# DIY_037.net
KiCad netlist of a schematic drawn in EAGLE
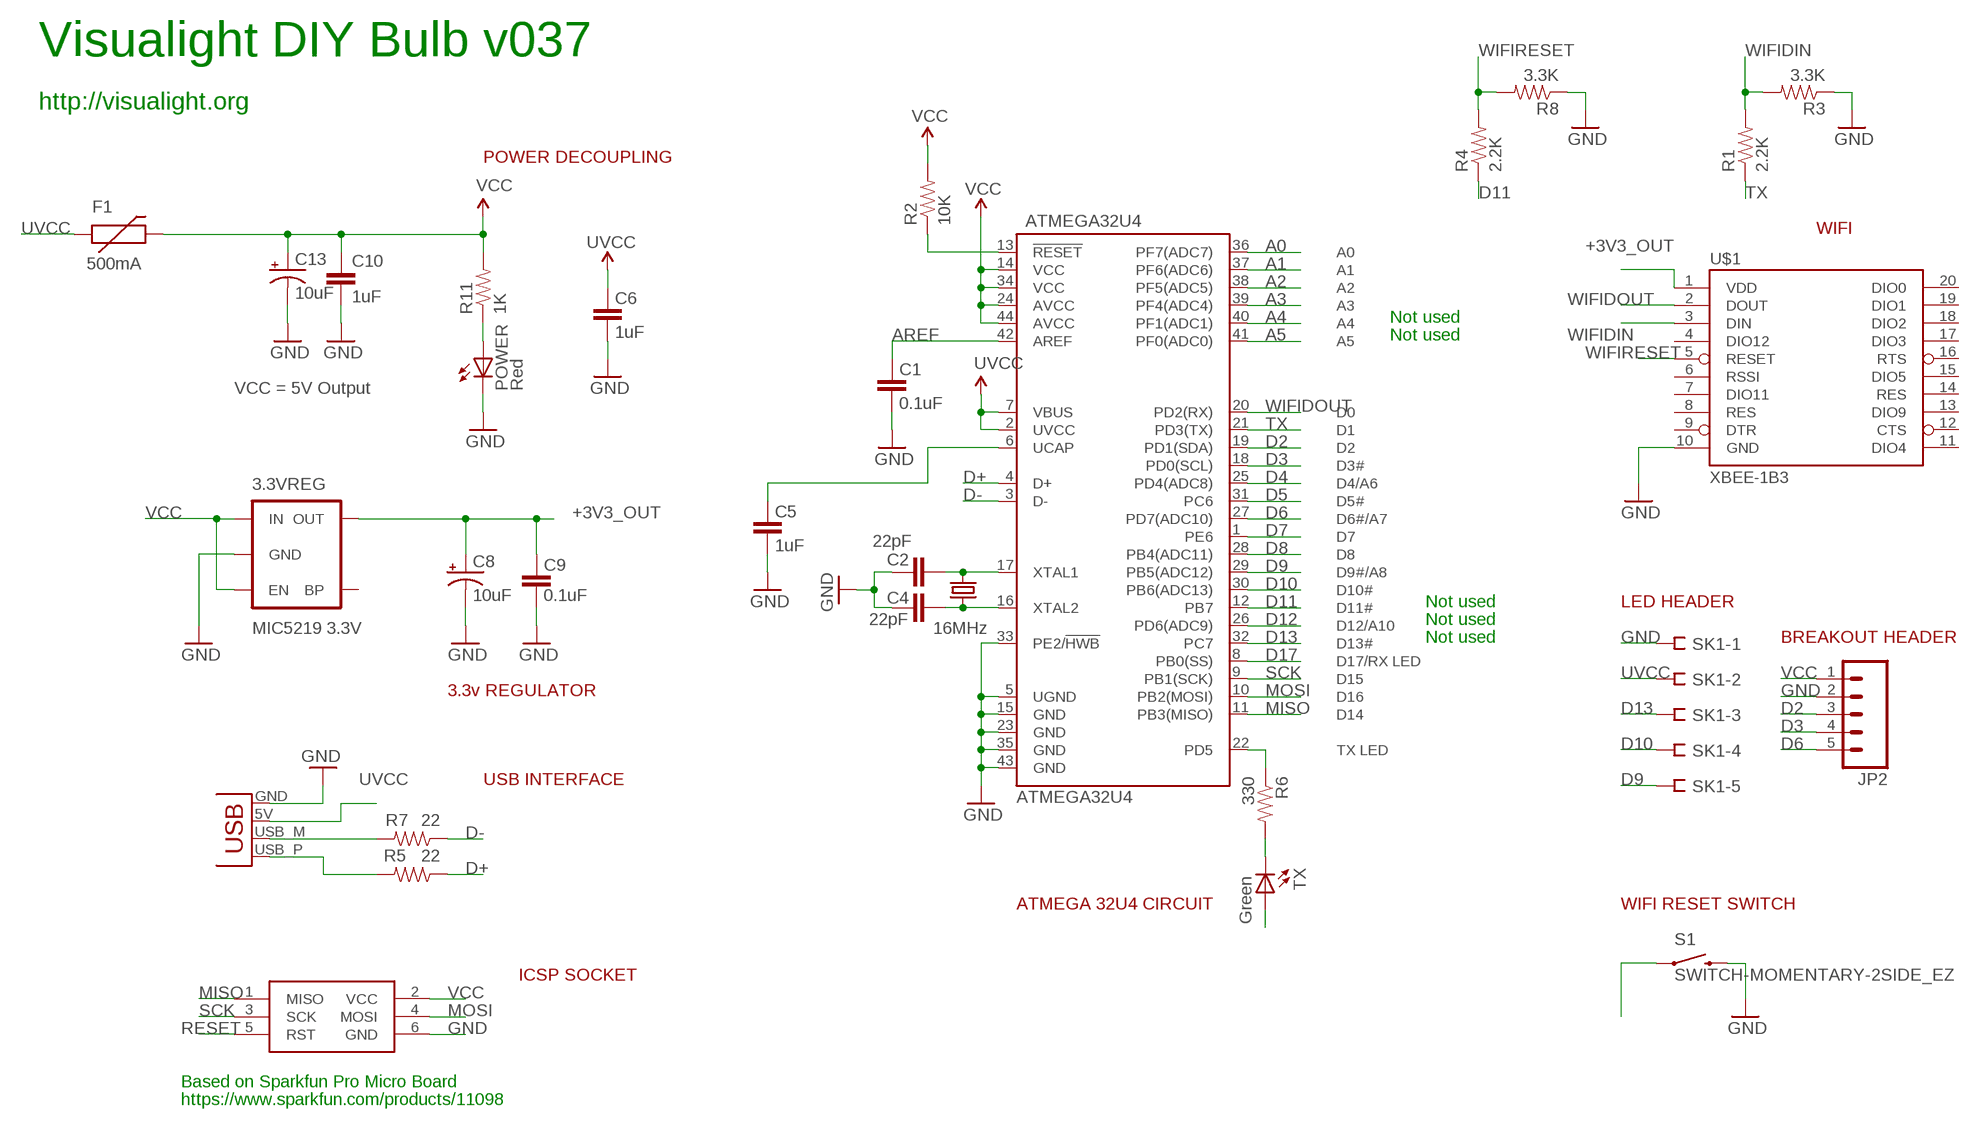
[diagram p0: schematic, sheet 1]

(export (version "E")
  (design (tool "Eeschema 10.0.6"))
  (components
    (comp (ref "3.3VREG")
      (value "MIC5219 3.3V")
      (footprint "eagle-import:SOT23-5")
      (libsource (lib "eagle-import") (part "V_REG_MIC52193.3V"))
    )
    (comp (ref "ATMEGA32U4")
      (value "ATMEGA32U4")
      (footprint "eagle-import:SPARKFUN-DIGITALIC_TQFP44")
      (libsource (lib "eagle-import") (part "ATMEGA32U4TQFP"))
    )
    (comp (ref "C1")
      (value "0.1uF")
      (footprint "eagle-import:0402-CAP")
      (libsource (lib "eagle-import") (part "CAP0402-CAP"))
    )
    (comp (ref "C2")
      (value "22pF")
      (footprint "eagle-import:0402-CAP")
      (libsource (lib "eagle-import") (part "CAP0402-CAP"))
    )
    (comp (ref "C4")
      (value "22pF")
      (footprint "eagle-import:0402-CAP")
      (libsource (lib "eagle-import") (part "CAP0402-CAP"))
    )
    (comp (ref "C5")
      (value "1uF")
      (footprint "eagle-import:0402-CAP")
      (libsource (lib "eagle-import") (part "CAP0402-CAP"))
    )
    (comp (ref "C6")
      (value "1uF")
      (footprint "eagle-import:0402-CAP")
      (libsource (lib "eagle-import") (part "CAP0402-CAP"))
    )
    (comp (ref "C8")
      (value "10uF")
      (footprint "eagle-import:EIA3216")
      (libsource (lib "eagle-import") (part "CAP_POL1206"))
    )
    (comp (ref "C9")
      (value "0.1uF")
      (footprint "eagle-import:0402-CAP")
      (libsource (lib "eagle-import") (part "CAP0402-CAP"))
    )
    (comp (ref "C10")
      (value "1uF")
      (footprint "eagle-import:0402-CAP")
      (libsource (lib "eagle-import") (part "CAP0402-CAP"))
    )
    (comp (ref "C13")
      (value "10uF")
      (footprint "eagle-import:EIA3216")
      (libsource (lib "eagle-import") (part "CAP_POL1206"))
    )
    (comp (ref "F1")
      (value "500mA")
      (footprint "eagle-import:PTC-1206")
      (libsource (lib "eagle-import") (part "PTCSMD"))
    )
    (comp (ref "ISP1")
      (value "AVRISP-6")
      (footprint "eagle-import:AVRISP")
      (libsource (lib "eagle-import") (part "AVRISP-6"))
    )
    (comp (ref "JP2")
      (value "M05PTH")
      (footprint "eagle-import:1X05")
      (libsource (lib "eagle-import") (part "M05PTH"))
    )
    (comp (ref "POWER")
      (value "Red")
      (footprint "eagle-import:LED-0603")
      (libsource (lib "eagle-import") (part "LED0603"))
    )
    (comp (ref "R1")
      (value "2.2K")
      (footprint "eagle-import:0402-RES")
      (libsource (lib "eagle-import") (part "RESISTOR0402-RES"))
    )
    (comp (ref "R2")
      (value "10K")
      (footprint "eagle-import:0402-RES")
      (libsource (lib "eagle-import") (part "RESISTOR0402-RES"))
    )
    (comp (ref "R3")
      (value "3.3K")
      (footprint "eagle-import:0402-RES")
      (libsource (lib "eagle-import") (part "RESISTOR0402-RES"))
    )
    (comp (ref "R4")
      (value "2.2K")
      (footprint "eagle-import:0402-RES")
      (libsource (lib "eagle-import") (part "RESISTOR0402-RES"))
    )
    (comp (ref "R5")
      (value "22")
      (footprint "eagle-import:0402-RES")
      (libsource (lib "eagle-import") (part "RESISTOR0402-RES"))
    )
    (comp (ref "R6")
      (value "330")
      (footprint "eagle-import:0402-RES")
      (libsource (lib "eagle-import") (part "RESISTOR0402-RES"))
    )
    (comp (ref "R7")
      (value "22")
      (footprint "eagle-import:0402-RES")
      (libsource (lib "eagle-import") (part "RESISTOR0402-RES"))
    )
    (comp (ref "R8")
      (value "3.3K")
      (footprint "eagle-import:0402-RES")
      (libsource (lib "eagle-import") (part "RESISTOR0402-RES"))
    )
    (comp (ref "R11")
      (value "1K")
      (footprint "eagle-import:0402-RES")
      (libsource (lib "eagle-import") (part "RESISTOR0402-RES"))
    )
    (comp (ref "S1")
      (value "SWITCH-MOMENTARY-2SIDE_EZ")
      (footprint "eagle-import:TACTILE-PTH-SIDEEZ")
      (libsource (lib "eagle-import") (part "SWITCH-MOMENTARY-2SIDE_EZ"))
    )
    (comp (ref "SK1")
      (value "DF3-05S")
      (footprint "eagle-import:DF3S-05")
      (libsource (lib "eagle-import") (part "DF3-05S"))
    )
    (comp (ref "TX")
      (value "Green")
      (footprint "eagle-import:LED-0603")
      (libsource (lib "eagle-import") (part "LED0603"))
    )
    (comp (ref "U$1")
      (value "XBEE-1B3")
      (footprint "eagle-import:XBEE-SMD")
      (libsource (lib "eagle-import") (part "XBEE-1B3"))
    )
    (comp (ref "X2")
      (value "USBPCB")
      (footprint "eagle-import:USB-A-PCB")
      (libsource (lib "eagle-import") (part "USBPCB"))
    )
    (comp (ref "Y1")
      (value "16MHz")
      (footprint "eagle-import:CRYSTAL-SMD-5X3")
      (libsource (lib "eagle-import") (part "CRYSTAL5X3"))
    )
  )
  (nets
    (net (code "1") (name "/+3V3_OUT") (class "Default")
      (node (ref "3.3VREG") (pin "5") (pinfunction "OUT_5") (pintype "passive"))
      (node (ref "C8") (pin "A") (pinfunction "+_A") (pintype "passive"))
      (node (ref "C9") (pin "2") (pinfunction "2_2") (pintype "passive"))
      (node (ref "U$1") (pin "1") (pinfunction "VDD_1") (pintype "power_in"))
    )
    (net (code "2") (name "/A0") (class "Default")
      (node (ref "ATMEGA32U4") (pin "36") (pinfunction "PF7(ADC7)_36") (pintype "bidirectional"))
    )
    (net (code "3") (name "/A1") (class "Default")
      (node (ref "ATMEGA32U4") (pin "37") (pinfunction "PF6(ADC6)_37") (pintype "bidirectional"))
    )
    (net (code "4") (name "/A2") (class "Default")
      (node (ref "ATMEGA32U4") (pin "38") (pinfunction "PF5(ADC5)_38") (pintype "bidirectional"))
    )
    (net (code "5") (name "/A3") (class "Default")
      (node (ref "ATMEGA32U4") (pin "39") (pinfunction "PF4(ADC4)_39") (pintype "bidirectional"))
    )
    (net (code "6") (name "/A4") (class "Default")
      (node (ref "ATMEGA32U4") (pin "40") (pinfunction "PF1(ADC1)_40") (pintype "bidirectional"))
    )
    (net (code "7") (name "/A5") (class "Default")
      (node (ref "ATMEGA32U4") (pin "41") (pinfunction "PF0(ADC0)_41") (pintype "bidirectional"))
    )
    (net (code "8") (name "/AREF") (class "Default")
      (node (ref "ATMEGA32U4") (pin "42") (pinfunction "AREF_42") (pintype "bidirectional"))
      (node (ref "C1") (pin "2") (pinfunction "2_2") (pintype "passive"))
    )
    (net (code "9") (name "/D+") (class "Default")
      (node (ref "ATMEGA32U4") (pin "4") (pinfunction "D+_4") (pintype "bidirectional"))
      (node (ref "R5") (pin "1") (pinfunction "1_1") (pintype "passive"))
    )
    (net (code "10") (name "/D-") (class "Default")
      (node (ref "ATMEGA32U4") (pin "3") (pinfunction "D-_3") (pintype "bidirectional"))
      (node (ref "R7") (pin "1") (pinfunction "1_1") (pintype "passive"))
    )
    (net (code "11") (name "/D2") (class "Default")
      (node (ref "ATMEGA32U4") (pin "19") (pinfunction "PD1(SDA)_19") (pintype "bidirectional"))
      (node (ref "JP2") (pin "3") (pinfunction "3_3") (pintype "passive"))
    )
    (net (code "12") (name "/D3") (class "Default")
      (node (ref "ATMEGA32U4") (pin "18") (pinfunction "PD0(SCL)_18") (pintype "bidirectional"))
      (node (ref "JP2") (pin "4") (pinfunction "4_4") (pintype "passive"))
    )
    (net (code "13") (name "/D4") (class "Default")
      (node (ref "ATMEGA32U4") (pin "25") (pinfunction "PD4(ADC8)_25") (pintype "bidirectional"))
    )
    (net (code "14") (name "/D5") (class "Default")
      (node (ref "ATMEGA32U4") (pin "31") (pinfunction "PC6_31") (pintype "bidirectional"))
    )
    (net (code "15") (name "/D6") (class "Default")
      (node (ref "ATMEGA32U4") (pin "27") (pinfunction "PD7(ADC10)_27") (pintype "bidirectional"))
      (node (ref "JP2") (pin "5") (pinfunction "5_5") (pintype "passive"))
    )
    (net (code "16") (name "/D7") (class "Default")
      (node (ref "ATMEGA32U4") (pin "1") (pinfunction "PE6_1") (pintype "bidirectional"))
      (node (ref "S1") (pin "1") (pinfunction "1_1") (pintype "passive"))
    )
    (net (code "17") (name "/D8") (class "Default")
      (node (ref "ATMEGA32U4") (pin "28") (pinfunction "PB4(ADC11)_28") (pintype "bidirectional"))
    )
    (net (code "18") (name "/D9") (class "Default")
      (node (ref "ATMEGA32U4") (pin "29") (pinfunction "PB5(ADC12)_29") (pintype "bidirectional"))
      (node (ref "SK1") (pin "5") (pinfunction "S_5") (pintype "passive"))
    )
    (net (code "19") (name "/D10") (class "Default")
      (node (ref "ATMEGA32U4") (pin "30") (pinfunction "PB6(ADC13)_30") (pintype "bidirectional"))
      (node (ref "SK1") (pin "4") (pinfunction "S_4") (pintype "passive"))
    )
    (net (code "20") (name "/D11") (class "Default")
      (node (ref "ATMEGA32U4") (pin "12") (pinfunction "PB7_12") (pintype "bidirectional"))
      (node (ref "R4") (pin "1") (pinfunction "1_1") (pintype "passive"))
    )
    (net (code "21") (name "/D12") (class "Default")
      (node (ref "ATMEGA32U4") (pin "26") (pinfunction "PD6(ADC9)_26") (pintype "bidirectional"))
    )
    (net (code "22") (name "/D13") (class "Default")
      (node (ref "ATMEGA32U4") (pin "32") (pinfunction "PC7_32") (pintype "bidirectional"))
      (node (ref "SK1") (pin "3") (pinfunction "S_3") (pintype "passive"))
    )
    (net (code "23") (name "/D17") (class "Default")
      (node (ref "ATMEGA32U4") (pin "8") (pinfunction "PB0(SS)_8") (pintype "bidirectional"))
    )
    (net (code "24") (name "/MISO") (class "Default")
      (node (ref "ATMEGA32U4") (pin "11") (pinfunction "PB3(MISO)_11") (pintype "bidirectional"))
      (node (ref "ISP1") (pin "1") (pinfunction "MISO_1") (pintype "input"))
    )
    (net (code "25") (name "/MOSI") (class "Default")
      (node (ref "ATMEGA32U4") (pin "10") (pinfunction "PB2(MOSI)_10") (pintype "bidirectional"))
      (node (ref "ISP1") (pin "4") (pinfunction "MOSI_4") (pintype "output"))
    )
    (net (code "26") (name "/RESET") (class "Default")
      (node (ref "ATMEGA32U4") (pin "13") (pinfunction "~{RESET}_13") (pintype "bidirectional"))
      (node (ref "ISP1") (pin "5") (pinfunction "RST_5") (pintype "output"))
      (node (ref "R2") (pin "1") (pinfunction "1_1") (pintype "passive"))
    )
    (net (code "27") (name "/SCK") (class "Default")
      (node (ref "ATMEGA32U4") (pin "9") (pinfunction "PB1(SCK)_9") (pintype "bidirectional"))
      (node (ref "ISP1") (pin "3") (pinfunction "SCK_3") (pintype "output"))
    )
    (net (code "28") (name "/TX") (class "Default")
      (node (ref "ATMEGA32U4") (pin "21") (pinfunction "PD3(TX)_21") (pintype "bidirectional"))
      (node (ref "R1") (pin "1") (pinfunction "1_1") (pintype "passive"))
    )
    (net (code "29") (name "/WIFIDIN") (class "Default")
      (node (ref "R1") (pin "2") (pinfunction "2_2") (pintype "passive"))
      (node (ref "R3") (pin "2") (pinfunction "2_2") (pintype "passive"))
      (node (ref "U$1") (pin "3") (pinfunction "DIN_3") (pintype "input"))
    )
    (net (code "30") (name "/WIFIDOUT") (class "Default")
      (node (ref "ATMEGA32U4") (pin "20") (pinfunction "PD2(RX)_20") (pintype "bidirectional"))
      (node (ref "U$1") (pin "2") (pinfunction "DOUT_2") (pintype "output"))
    )
    (net (code "31") (name "/WIFIRESET") (class "Default")
      (node (ref "R4") (pin "2") (pinfunction "2_2") (pintype "passive"))
      (node (ref "R8") (pin "2") (pinfunction "2_2") (pintype "passive"))
      (node (ref "U$1") (pin "5") (pinfunction "RESET_5") (pintype "input"))
    )
    (net (code "32") (name "GND") (class "Default")
      (node (ref "3.3VREG") (pin "2") (pinfunction "GND_2") (pintype "input"))
      (node (ref "ATMEGA32U4") (pin "15") (pinfunction "GND_15") (pintype "bidirectional"))
      (node (ref "ATMEGA32U4") (pin "23") (pinfunction "GND_23") (pintype "bidirectional"))
      (node (ref "ATMEGA32U4") (pin "33") (pinfunction "PE2/~{HWB}_33") (pintype "bidirectional"))
      (node (ref "ATMEGA32U4") (pin "35") (pinfunction "GND_35") (pintype "bidirectional"))
      (node (ref "ATMEGA32U4") (pin "43") (pinfunction "GND_43") (pintype "bidirectional"))
      (node (ref "ATMEGA32U4") (pin "5") (pinfunction "UGND_5") (pintype "bidirectional"))
      (node (ref "C1") (pin "1") (pinfunction "1_1") (pintype "passive"))
      (node (ref "C10") (pin "2") (pinfunction "2_2") (pintype "passive"))
      (node (ref "C13") (pin "C") (pinfunction "-_C") (pintype "passive"))
      (node (ref "C2") (pin "2") (pinfunction "2_2") (pintype "passive"))
      (node (ref "C4") (pin "2") (pinfunction "2_2") (pintype "passive"))
      (node (ref "C5") (pin "1") (pinfunction "1_1") (pintype "passive"))
      (node (ref "C6") (pin "1") (pinfunction "1_1") (pintype "passive"))
      (node (ref "C8") (pin "C") (pinfunction "-_C") (pintype "passive"))
      (node (ref "C9") (pin "1") (pinfunction "1_1") (pintype "passive"))
      (node (ref "ISP1") (pin "6") (pinfunction "GND_6") (pintype "power_in"))
      (node (ref "JP2") (pin "2") (pinfunction "2_2") (pintype "passive"))
      (node (ref "POWER") (pin "C") (pinfunction "C_C") (pintype "passive"))
      (node (ref "R3") (pin "1") (pinfunction "1_1") (pintype "passive"))
      (node (ref "R8") (pin "1") (pinfunction "1_1") (pintype "passive"))
      (node (ref "S1") (pin "2") (pinfunction "2_2") (pintype "passive"))
      (node (ref "SK1") (pin "1") (pinfunction "S_1") (pintype "passive"))
      (node (ref "U$1") (pin "10") (pinfunction "GND_10") (pintype "power_in"))
      (node (ref "X2") (pin "GND") (pinfunction "GND_GND") (pintype "bidirectional"))
    )
    (net (code "33") (name "Net-(ATMEGA32U4-PD5)") (class "Default")
      (node (ref "ATMEGA32U4") (pin "22") (pinfunction "PD5_22") (pintype "bidirectional"))
      (node (ref "R6") (pin "1") (pinfunction "1_1") (pintype "passive"))
    )
    (net (code "34") (name "Net-(ATMEGA32U4-UCAP)") (class "Default")
      (node (ref "ATMEGA32U4") (pin "6") (pinfunction "UCAP_6") (pintype "bidirectional"))
      (node (ref "C5") (pin "2") (pinfunction "2_2") (pintype "passive"))
    )
    (net (code "35") (name "Net-(ATMEGA32U4-XTAL1)") (class "Default")
      (node (ref "ATMEGA32U4") (pin "17") (pinfunction "XTAL1_17") (pintype "bidirectional"))
      (node (ref "C2") (pin "1") (pinfunction "1_1") (pintype "passive"))
      (node (ref "Y1") (pin "3") (pinfunction "2_3") (pintype "passive"))
    )
    (net (code "36") (name "Net-(ATMEGA32U4-XTAL2)") (class "Default")
      (node (ref "ATMEGA32U4") (pin "16") (pinfunction "XTAL2_16") (pintype "bidirectional"))
      (node (ref "C4") (pin "1") (pinfunction "1_1") (pintype "passive"))
      (node (ref "Y1") (pin "1") (pinfunction "1_1") (pintype "passive"))
    )
    (net (code "37") (name "Net-(POWER-PadA)") (class "Default")
      (node (ref "POWER") (pin "A") (pinfunction "A_A") (pintype "passive"))
      (node (ref "R11") (pin "1") (pinfunction "1_1") (pintype "passive"))
    )
    (net (code "38") (name "Net-(R6-Pad2)") (class "Default")
      (node (ref "R6") (pin "2") (pinfunction "2_2") (pintype "passive"))
      (node (ref "TX") (pin "C") (pinfunction "C_C") (pintype "passive"))
    )
    (net (code "39") (name "Net-(X2-D+)") (class "Default")
      (node (ref "R5") (pin "2") (pinfunction "2_2") (pintype "passive"))
      (node (ref "X2") (pin "USB_P") (pinfunction "D+_USB_P") (pintype "bidirectional"))
    )
    (net (code "40") (name "Net-(X2-D-)") (class "Default")
      (node (ref "R7") (pin "2") (pinfunction "2_2") (pintype "passive"))
      (node (ref "X2") (pin "USB_M") (pinfunction "D-_USB_M") (pintype "bidirectional"))
    )
    (net (code "41") (name "UVCC") (class "Default")
      (node (ref "ATMEGA32U4") (pin "2") (pinfunction "UVCC_2") (pintype "bidirectional"))
      (node (ref "ATMEGA32U4") (pin "7") (pinfunction "VBUS_7") (pintype "bidirectional"))
      (node (ref "C6") (pin "2") (pinfunction "2_2") (pintype "passive"))
      (node (ref "F1") (pin "1") (pinfunction "1_1") (pintype "bidirectional"))
      (node (ref "SK1") (pin "2") (pinfunction "S_2") (pintype "passive"))
      (node (ref "X2") (pin "5V") (pinfunction "VBUS_5V") (pintype "bidirectional"))
    )
    (net (code "42") (name "VCC") (class "Default")
      (node (ref "3.3VREG") (pin "1") (pinfunction "IN_1") (pintype "input"))
      (node (ref "3.3VREG") (pin "3") (pinfunction "EN_3") (pintype "input"))
      (node (ref "ATMEGA32U4") (pin "14") (pinfunction "VCC_14") (pintype "bidirectional"))
      (node (ref "ATMEGA32U4") (pin "24") (pinfunction "AVCC_24") (pintype "bidirectional"))
      (node (ref "ATMEGA32U4") (pin "34") (pinfunction "VCC_34") (pintype "bidirectional"))
      (node (ref "ATMEGA32U4") (pin "44") (pinfunction "AVCC_44") (pintype "bidirectional"))
      (node (ref "C10") (pin "1") (pinfunction "1_1") (pintype "passive"))
      (node (ref "C13") (pin "A") (pinfunction "+_A") (pintype "passive"))
      (node (ref "F1") (pin "2") (pinfunction "2_2") (pintype "bidirectional"))
      (node (ref "ISP1") (pin "2") (pinfunction "VCC_2") (pintype "power_in"))
      (node (ref "JP2") (pin "1") (pinfunction "1_1") (pintype "passive"))
      (node (ref "R11") (pin "2") (pinfunction "2_2") (pintype "passive"))
      (node (ref "R2") (pin "2") (pinfunction "2_2") (pintype "passive"))
      (node (ref "TX") (pin "A") (pinfunction "A_A") (pintype "passive"))
    )
    (net (code "43") (name "unconnected-(3.3VREG-BP-Pad4)") (class "Default")
      (node (ref "3.3VREG") (pin "4") (pinfunction "BP_4") (pintype "input"))
    )
    (net (code "44") (name "unconnected-(U$1-CTS-Pad12)") (class "Default")
      (node (ref "U$1") (pin "12") (pinfunction "CTS_12") (pintype "output"))
    )
    (net (code "45") (name "unconnected-(U$1-DIO0-Pad20)") (class "Default")
      (node (ref "U$1") (pin "20") (pinfunction "DIO0_20") (pintype "bidirectional"))
    )
    (net (code "46") (name "unconnected-(U$1-DIO1-Pad19)") (class "Default")
      (node (ref "U$1") (pin "19") (pinfunction "DIO1_19") (pintype "bidirectional"))
    )
    (net (code "47") (name "unconnected-(U$1-DIO2-Pad18)") (class "Default")
      (node (ref "U$1") (pin "18") (pinfunction "DIO2_18") (pintype "bidirectional"))
    )
    (net (code "48") (name "unconnected-(U$1-DIO3-Pad17)") (class "Default")
      (node (ref "U$1") (pin "17") (pinfunction "DIO3_17") (pintype "bidirectional"))
    )
    (net (code "49") (name "unconnected-(U$1-DIO4-Pad11)") (class "Default")
      (node (ref "U$1") (pin "11") (pinfunction "DIO4_11") (pintype "bidirectional"))
    )
    (net (code "50") (name "unconnected-(U$1-DIO5-Pad15)") (class "Default")
      (node (ref "U$1") (pin "15") (pinfunction "DIO5_15") (pintype "bidirectional"))
    )
    (net (code "51") (name "unconnected-(U$1-DIO9-Pad13)") (class "Default")
      (node (ref "U$1") (pin "13") (pinfunction "DIO9_13") (pintype "bidirectional"))
    )
    (net (code "52") (name "unconnected-(U$1-DIO11-Pad7)") (class "Default")
      (node (ref "U$1") (pin "7") (pinfunction "DIO11_7") (pintype "bidirectional"))
    )
    (net (code "53") (name "unconnected-(U$1-DIO12-Pad4)") (class "Default")
      (node (ref "U$1") (pin "4") (pinfunction "DIO12_4") (pintype "bidirectional"))
    )
    (net (code "54") (name "unconnected-(U$1-DTR-Pad9)") (class "Default")
      (node (ref "U$1") (pin "9") (pinfunction "DTR_9") (pintype "bidirectional"))
    )
    (net (code "55") (name "unconnected-(U$1-RES-Pad8)") (class "Default")
      (node (ref "U$1") (pin "8") (pinfunction "RES_8") (pintype "bidirectional"))
    )
    (net (code "56") (name "unconnected-(U$1-RES-Pad14)") (class "Default")
      (node (ref "U$1") (pin "14") (pinfunction "RES_14") (pintype "bidirectional"))
    )
    (net (code "57") (name "unconnected-(U$1-RSSI-Pad6)") (class "Default")
      (node (ref "U$1") (pin "6") (pinfunction "RSSI_6") (pintype "bidirectional"))
    )
    (net (code "58") (name "unconnected-(U$1-RTS-Pad16)") (class "Default")
      (node (ref "U$1") (pin "16") (pinfunction "RTS_16") (pintype "input"))
    )
  )
)
